# Optical_RX.net
KiCad netlist of a schematic drawn in Altium Designer
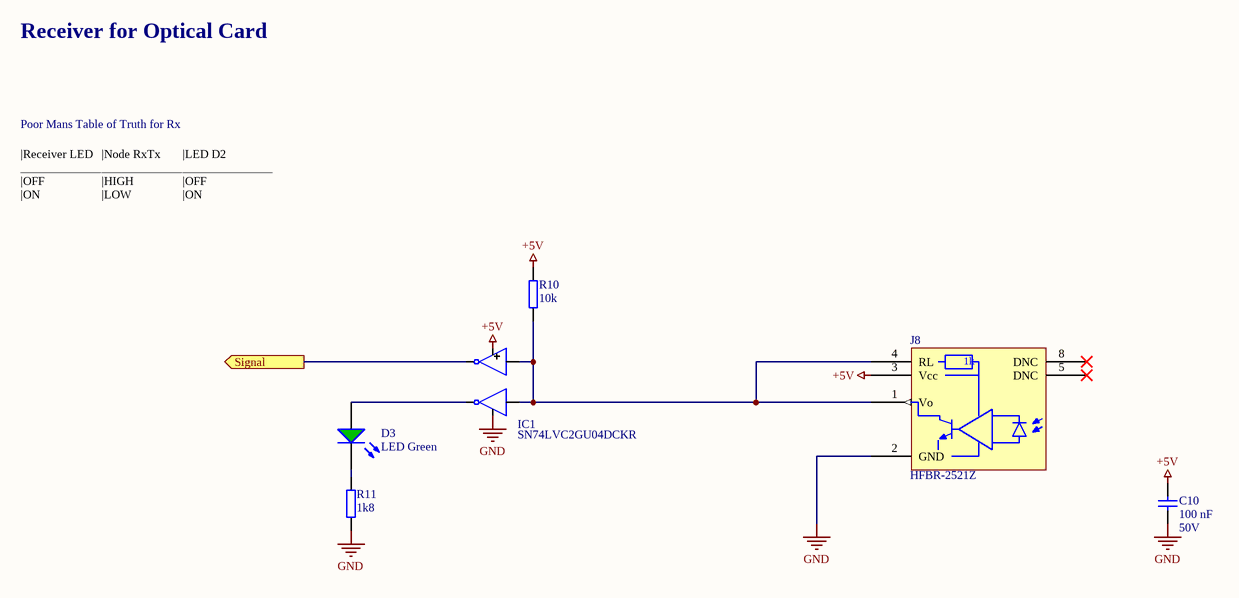
[diagram p0: Optical_RX.SchDoc]

(export (version "E")
  (design (tool "Eeschema 10.0.6"))
  (components
    (comp (ref "C10")
      (value "100 nF")
      (footprint "C_0603_TE")
      (description "Generic capacitor")
      (fields
        (field (name "MANUFACTURER PART NUMBER") "UZgen_C_0603_100nF_50V_X7R")
        (field (name "MANUFACTURER") "UZgen")
        (field (name "VOLTAGE") "50V")
        (field (name "CREATED FROM") "AGeiger")
      )
      (libsource (lib "user") (part "CAP-NP"))
    )
    (comp (ref "D3")
      (value "LED Green")
      (footprint "WL-SMCW_0603")
      (description "LED GREEN 520~535NM 112~258MCD@20MA TOP VIEW 0603 ROHS")
      (fields
        (field (name "MANUFACTURER PART NUMBER") "19-217/GHC-YR1S2/3T")
        (field (name "MANUFACTURER") "Everlight Elec")
        (field (name "CREATED FROM") "T. Wendt")
      )
      (libsource (lib "user") (part "LED_Green"))
    )
    (comp (ref "IC1")
      (value "SN74LVC2GU04DCKR")
      (footprint "SN74LVC2GU04DCKR")
      (description "Dual inverter designed for 1.65-V to 5.5-V VCC operation.")
      (fields
        (field (name "MANUFACTURER") "Texas Instruments")
        (field (name "LCSC PART NUMBER") "C116660")
        (field (name "CREATED FROM") "N.Diringer")
      )
      (libsource (lib "user") (part "SN74LVC2GU04DCKR"))
    )
    (comp (ref "J8")
      (value "HFBR-2521Z")
      (footprint "HFBRx5XX")
      (description "Fibre Optic Receivers, LINK HORIZ 5MBd RC VR RoHS")
      (fields
        (field (name "MF") "Boadcom/Avago")
        (field (name "MANUFACTURER") "Broadcom")
        (field (name "CREATED") "2019_04_09_Kreppel")
        (field (name "CREATED FROM") "VStarost")
      )
      (libsource (lib "user") (part "HFBR-2528Z"))
    )
    (comp (ref "R10")
      (value "10k")
      (footprint "R_0603_TE")
      (description "Generic resistor")
      (fields
        (field (name "MANUFACTURER PART NUMBER") "UZgen_R_0603_10k")
        (field (name "MANUFACTURER") "UZgen")
        (field (name "CREATED FROM") "AGeiger")
      )
      (libsource (lib "user") (part "RES"))
    )
    (comp (ref "R11")
      (value "1k8")
      (footprint "R_0603_TE")
      (description "Generic resistor")
      (fields
        (field (name "MANUFACTURER PART NUMBER") "UZgen_R_0603_1k8")
        (field (name "MANUFACTURER") "UZgen")
        (field (name "CREATED FROM") "UZgenTool")
      )
      (libsource (lib "user") (part "RES"))
    )
  )
  (nets
    (net (code "1") (name "+5V") (class "Default")
      (node (ref "C10") (pin "2") (pinfunction "2_2") (pintype "passive"))
      (node (ref "IC1") (pin "5") (pinfunction "VCC_5") (pintype "passive"))
      (node (ref "J8") (pin "3") (pinfunction "Vcc_3") (pintype "power_in"))
      (node (ref "R10") (pin "1") (pinfunction "1_1") (pintype "passive"))
    )
    (net (code "2") (name "/Signal") (class "Default")
      (node (ref "IC1") (pin "6") (pinfunction "OUT2_6") (pintype "passive"))
    )
    (net (code "3") (name "GND") (class "Default")
      (node (ref "C10") (pin "1") (pinfunction "1_1") (pintype "passive"))
      (node (ref "IC1") (pin "2") (pinfunction "GND_2") (pintype "passive"))
      (node (ref "J8") (pin "2") (pinfunction "GND_2") (pintype "power_in"))
      (node (ref "R11") (pin "2") (pinfunction "2_2") (pintype "passive"))
    )
    (net (code "4") (name "Net-(D3-A)") (class "Default")
      (node (ref "D3") (pin "2") (pinfunction "A_2") (pintype "passive"))
      (node (ref "IC1") (pin "4") (pinfunction "OUT2_4") (pintype "passive"))
    )
    (net (code "5") (name "Net-(D3-K)") (class "Default")
      (node (ref "D3") (pin "1") (pinfunction "K_1") (pintype "passive"))
      (node (ref "R11") (pin "1") (pinfunction "1_1") (pintype "passive"))
    )
    (net (code "6") (name "Net-(IC1-IN1)") (class "Default")
      (node (ref "IC1") (pin "1") (pinfunction "IN1_1") (pintype "passive"))
      (node (ref "IC1") (pin "3") (pinfunction "IN2_3") (pintype "passive"))
      (node (ref "J8") (pin "1") (pinfunction "Vo_1") (pintype "output"))
      (node (ref "J8") (pin "4") (pinfunction "RL_4") (pintype "passive"))
      (node (ref "R10") (pin "2") (pinfunction "2_2") (pintype "passive"))
    )
    (net (code "7") (name "unconnected-(J8-DNC-Pad5)") (class "Default")
      (node (ref "J8") (pin "5") (pinfunction "DNC_5") (pintype "passive+no_connect"))
    )
    (net (code "8") (name "unconnected-(J8-DNC-Pad8)") (class "Default")
      (node (ref "J8") (pin "8") (pinfunction "DNC_8") (pintype "passive+no_connect"))
    )
  )
)
